# jura.net
KiCad netlist of a schematic drawn in EAGLE
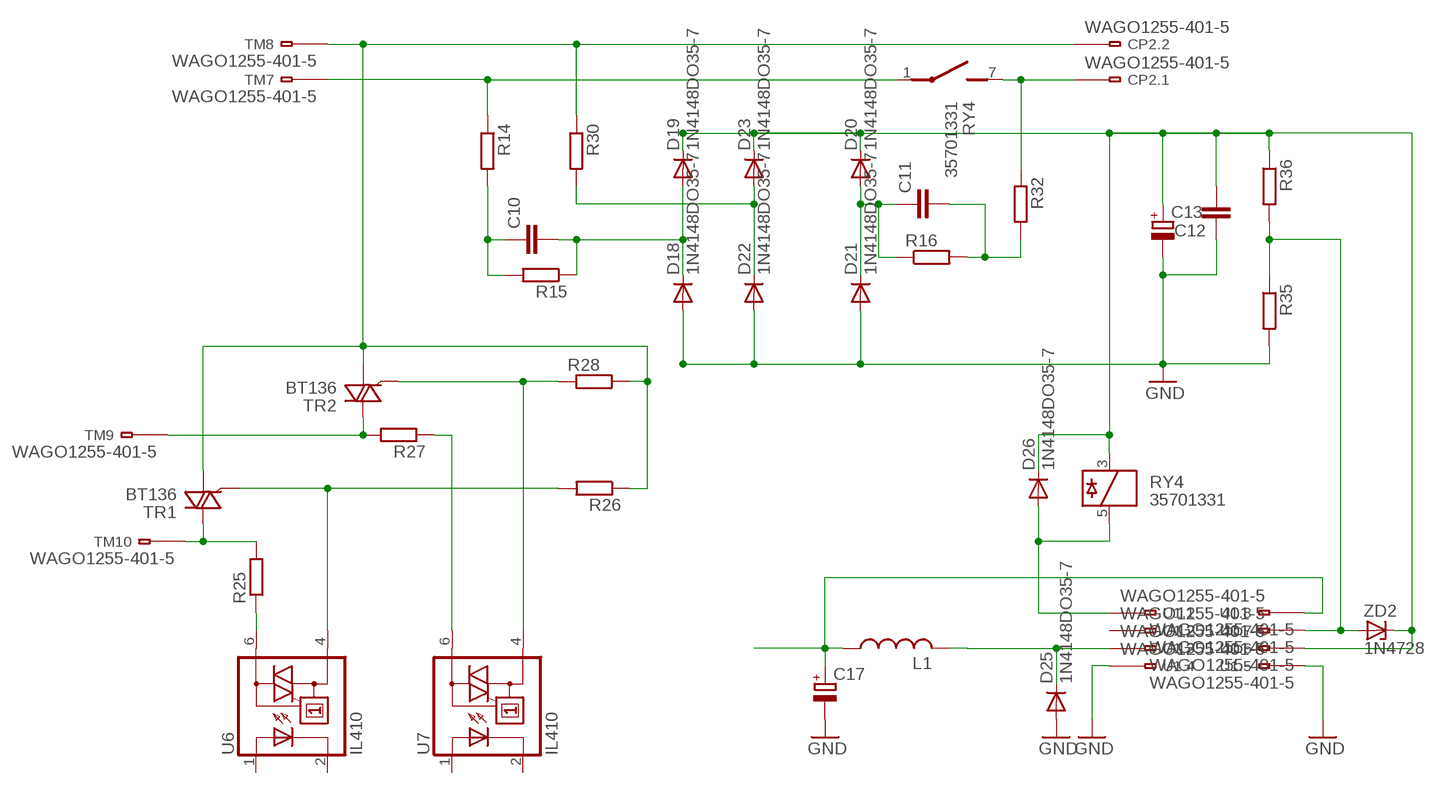
[diagram p0: schematic, sheet 1]

(export (version "E")
  (design (tool "Eeschema 10.0.6"))
  (components
    (comp (ref "C10")
      (value "C-EU025-025X050")
      (footprint "eagle-import:C025-025X050")
      (libsource (lib "eagle-import") (part "C-EU025-025X050"))
    )
    (comp (ref "C11")
      (value "C-EU025-025X050")
      (footprint "eagle-import:C025-025X050")
      (libsource (lib "eagle-import") (part "C-EU025-025X050"))
    )
    (comp (ref "C12")
      (value "C-EU025-025X050")
      (footprint "eagle-import:C025-025X050")
      (libsource (lib "eagle-import") (part "C-EU025-025X050"))
    )
    (comp (ref "C13")
      (value "CPOL-EUE2-4")
      (footprint "eagle-import:E2-4")
      (libsource (lib "eagle-import") (part "CPOL-EUE2-4"))
    )
    (comp (ref "C17")
      (value "CPOL-EUE2-4")
      (footprint "eagle-import:E2-4")
      (libsource (lib "eagle-import") (part "CPOL-EUE2-4"))
    )
    (comp (ref "CP2.1")
      (value "WAGO1255-401-5")
      (footprint "eagle-import:255-401-5")
      (fields (field (name "MPN") "255-401"))
      (libsource (lib "eagle-import") (part "WAGO1255-401-5"))
    )
    (comp (ref "CP2.2")
      (value "WAGO1255-401-5")
      (footprint "eagle-import:255-401-5")
      (fields (field (name "MPN") "255-401"))
      (libsource (lib "eagle-import") (part "WAGO1255-401-5"))
    )
    (comp (ref "D18")
      (value "1N4148DO35-7")
      (footprint "eagle-import:DO35-7")
      (libsource (lib "eagle-import") (part "1N4148DO35-7"))
    )
    (comp (ref "D19")
      (value "1N4148DO35-7")
      (footprint "eagle-import:DO35-7")
      (libsource (lib "eagle-import") (part "1N4148DO35-7"))
    )
    (comp (ref "D20")
      (value "1N4148DO35-7")
      (footprint "eagle-import:DO35-7")
      (libsource (lib "eagle-import") (part "1N4148DO35-7"))
    )
    (comp (ref "D21")
      (value "1N4148DO35-7")
      (footprint "eagle-import:DO35-7")
      (libsource (lib "eagle-import") (part "1N4148DO35-7"))
    )
    (comp (ref "D22")
      (value "1N4148DO35-7")
      (footprint "eagle-import:DO35-7")
      (libsource (lib "eagle-import") (part "1N4148DO35-7"))
    )
    (comp (ref "D23")
      (value "1N4148DO35-7")
      (footprint "eagle-import:DO35-7")
      (libsource (lib "eagle-import") (part "1N4148DO35-7"))
    )
    (comp (ref "D25")
      (value "1N4148DO35-7")
      (footprint "eagle-import:DO35-7")
      (libsource (lib "eagle-import") (part "1N4148DO35-7"))
    )
    (comp (ref "D26")
      (value "1N4148DO35-7")
      (footprint "eagle-import:DO35-7")
      (libsource (lib "eagle-import") (part "1N4148DO35-7"))
    )
    (comp (ref "L1")
      (value "L-US0204/7")
      (footprint "eagle-import:0204_7")
      (libsource (lib "eagle-import") (part "L-US0204/7"))
    )
    (comp (ref "R14")
      (value "R-EU_0204/7")
      (footprint "eagle-import:0204_7")
      (libsource (lib "eagle-import") (part "R-EU_0204/7"))
    )
    (comp (ref "R15")
      (value "R-EU_0204/7")
      (footprint "eagle-import:0204_7")
      (libsource (lib "eagle-import") (part "R-EU_0204/7"))
    )
    (comp (ref "R16")
      (value "R-EU_0204/7")
      (footprint "eagle-import:0204_7")
      (libsource (lib "eagle-import") (part "R-EU_0204/7"))
    )
    (comp (ref "R25")
      (value "R-EU_0204/7")
      (footprint "eagle-import:0204_7")
      (libsource (lib "eagle-import") (part "R-EU_0204/7"))
    )
    (comp (ref "R26")
      (value "R-EU_0204/7")
      (footprint "eagle-import:0204_7")
      (libsource (lib "eagle-import") (part "R-EU_0204/7"))
    )
    (comp (ref "R27")
      (value "R-EU_0204/7")
      (footprint "eagle-import:0204_7")
      (libsource (lib "eagle-import") (part "R-EU_0204/7"))
    )
    (comp (ref "R28")
      (value "R-EU_0204/7")
      (footprint "eagle-import:0204_7")
      (libsource (lib "eagle-import") (part "R-EU_0204/7"))
    )
    (comp (ref "R30")
      (value "R-EU_0204/7")
      (footprint "eagle-import:0204_7")
      (libsource (lib "eagle-import") (part "R-EU_0204/7"))
    )
    (comp (ref "R32")
      (value "R-EU_0204/7")
      (footprint "eagle-import:0204_7")
      (libsource (lib "eagle-import") (part "R-EU_0204/7"))
    )
    (comp (ref "R35")
      (value "R-EU_0204/7")
      (footprint "eagle-import:0204_7")
      (libsource (lib "eagle-import") (part "R-EU_0204/7"))
    )
    (comp (ref "R36")
      (value "R-EU_0204/7")
      (footprint "eagle-import:0204_7")
      (libsource (lib "eagle-import") (part "R-EU_0204/7"))
    )
    (comp (ref "RY4")
      (value "35701331")
      (footprint "eagle-import:REED")
      (libsource (lib "eagle-import") (part "35701331"))
    )
    (comp (ref "TM7")
      (value "WAGO1255-401-5")
      (footprint "eagle-import:255-401-5")
      (fields (field (name "MPN") "255-401"))
      (libsource (lib "eagle-import") (part "WAGO1255-401-5"))
    )
    (comp (ref "TM8")
      (value "WAGO1255-401-5")
      (footprint "eagle-import:255-401-5")
      (fields (field (name "MPN") "255-401"))
      (libsource (lib "eagle-import") (part "WAGO1255-401-5"))
    )
    (comp (ref "TM9")
      (value "WAGO1255-401-5")
      (footprint "eagle-import:255-401-5")
      (fields (field (name "MPN") "255-401"))
      (libsource (lib "eagle-import") (part "WAGO1255-401-5"))
    )
    (comp (ref "TM10")
      (value "WAGO1255-401-5")
      (footprint "eagle-import:255-401-5")
      (fields (field (name "MPN") "255-401"))
      (libsource (lib "eagle-import") (part "WAGO1255-401-5"))
    )
    (comp (ref "TR1")
      (value "BT136")
      (footprint "eagle-import:TO220AB")
      (libsource (lib "eagle-import") (part "BT136"))
    )
    (comp (ref "TR2")
      (value "BT136")
      (footprint "eagle-import:TO220AB")
      (libsource (lib "eagle-import") (part "BT136"))
    )
    (comp (ref "U1.1")
      (value "WAGO1255-401-5")
      (footprint "eagle-import:255-401-5")
      (fields (field (name "MPN") "255-401"))
      (libsource (lib "eagle-import") (part "WAGO1255-401-5"))
    )
    (comp (ref "U1.2")
      (value "WAGO1255-401-5")
      (footprint "eagle-import:255-401-5")
      (fields (field (name "MPN") "255-401"))
      (libsource (lib "eagle-import") (part "WAGO1255-401-5"))
    )
    (comp (ref "U1.3")
      (value "WAGO1255-401-5")
      (footprint "eagle-import:255-401-5")
      (fields (field (name "MPN") "255-401"))
      (libsource (lib "eagle-import") (part "WAGO1255-401-5"))
    )
    (comp (ref "U1.4")
      (value "WAGO1255-401-5")
      (footprint "eagle-import:255-401-5")
      (fields (field (name "MPN") "255-401"))
      (libsource (lib "eagle-import") (part "WAGO1255-401-5"))
    )
    (comp (ref "U1.5")
      (value "WAGO1255-401-5")
      (footprint "eagle-import:255-401-5")
      (fields (field (name "MPN") "255-401"))
      (libsource (lib "eagle-import") (part "WAGO1255-401-5"))
    )
    (comp (ref "U1.6")
      (value "WAGO1255-401-5")
      (footprint "eagle-import:255-401-5")
      (fields (field (name "MPN") "255-401"))
      (libsource (lib "eagle-import") (part "WAGO1255-401-5"))
    )
    (comp (ref "U1.7")
      (value "WAGO1255-401-5")
      (footprint "eagle-import:255-401-5")
      (fields (field (name "MPN") "255-401"))
      (libsource (lib "eagle-import") (part "WAGO1255-401-5"))
    )
    (comp (ref "U1.8")
      (value "WAGO1255-401-5")
      (footprint "eagle-import:255-401-5")
      (fields (field (name "MPN") "255-401"))
      (libsource (lib "eagle-import") (part "WAGO1255-401-5"))
    )
    (comp (ref "U6")
      (value "IL410")
      (footprint "eagle-import:DIL06")
      (fields (field (name "MF") "VISHAY/TELEFUNKEN"))
      (libsource (lib "eagle-import") (part "IL410"))
    )
    (comp (ref "U7")
      (value "IL410")
      (footprint "eagle-import:DIL06")
      (fields (field (name "MF") "VISHAY/TELEFUNKEN"))
      (libsource (lib "eagle-import") (part "IL410"))
    )
    (comp (ref "ZD2")
      (value "1N4728")
      (footprint "eagle-import:DO41Z10")
      (libsource (lib "eagle-import") (part "1N4728"))
    )
  )
  (nets
    (net (code "1") (name "GND") (class "Default")
      (node (ref "C12") (pin "1") (pinfunction "1_1") (pintype "passive"))
      (node (ref "C13") (pin "-") (pinfunction "-_-") (pintype "passive"))
      (node (ref "C17") (pin "-") (pinfunction "-_-") (pintype "passive"))
      (node (ref "D18") (pin "A") (pinfunction "A_A") (pintype "passive"))
      (node (ref "D21") (pin "A") (pinfunction "A_A") (pintype "passive"))
      (node (ref "D22") (pin "A") (pinfunction "A_A") (pintype "passive"))
      (node (ref "D25") (pin "A") (pinfunction "A_A") (pintype "passive"))
      (node (ref "R35") (pin "2") (pinfunction "2_2") (pintype "passive"))
      (node (ref "U1.4") (pin "B1") (pinfunction "B1_B1") (pintype "passive"))
      (node (ref "U1.5") (pin "B1") (pinfunction "B1_B1") (pintype "passive"))
    )
    (net (code "2") (name "Net-(C10-Pad1)") (class "Default")
      (node (ref "C10") (pin "1") (pinfunction "1_1") (pintype "passive"))
      (node (ref "R14") (pin "2") (pinfunction "2_2") (pintype "passive"))
      (node (ref "R15") (pin "2") (pinfunction "2_2") (pintype "passive"))
    )
    (net (code "3") (name "Net-(C10-Pad2)") (class "Default")
      (node (ref "C10") (pin "2") (pinfunction "2_2") (pintype "passive"))
      (node (ref "D18") (pin "C") (pinfunction "C_C") (pintype "passive"))
      (node (ref "D19") (pin "A") (pinfunction "A_A") (pintype "passive"))
      (node (ref "R15") (pin "1") (pinfunction "1_1") (pintype "passive"))
    )
    (net (code "4") (name "Net-(C11-Pad1)") (class "Default")
      (node (ref "C11") (pin "1") (pinfunction "1_1") (pintype "passive"))
      (node (ref "D20") (pin "A") (pinfunction "A_A") (pintype "passive"))
      (node (ref "D21") (pin "C") (pinfunction "C_C") (pintype "passive"))
      (node (ref "R16") (pin "1") (pinfunction "1_1") (pintype "passive"))
    )
    (net (code "5") (name "Net-(C11-Pad2)") (class "Default")
      (node (ref "C11") (pin "2") (pinfunction "2_2") (pintype "passive"))
      (node (ref "R16") (pin "2") (pinfunction "2_2") (pintype "passive"))
      (node (ref "R32") (pin "2") (pinfunction "2_2") (pintype "passive"))
    )
    (net (code "6") (name "Net-(C12-Pad2)") (class "Default")
      (node (ref "C12") (pin "2") (pinfunction "2_2") (pintype "passive"))
      (node (ref "C13") (pin "+") (pinfunction "+_+") (pintype "passive"))
      (node (ref "D19") (pin "C") (pinfunction "C_C") (pintype "passive"))
      (node (ref "D20") (pin "C") (pinfunction "C_C") (pintype "passive"))
      (node (ref "D23") (pin "C") (pinfunction "C_C") (pintype "passive"))
      (node (ref "D26") (pin "C") (pinfunction "C_C") (pintype "passive"))
      (node (ref "R36") (pin "1") (pinfunction "1_1") (pintype "passive"))
      (node (ref "RY4") (pin "3") (pinfunction "3_3") (pintype "passive"))
      (node (ref "U1.6") (pin "B1") (pinfunction "B1_B1") (pintype "passive"))
      (node (ref "ZD2") (pin "C") (pinfunction "C_C") (pintype "passive"))
    )
    (net (code "7") (name "Net-(C17-Pad+)") (class "Default")
      (node (ref "C17") (pin "+") (pinfunction "+_+") (pintype "passive"))
      (node (ref "L1") (pin "1") (pinfunction "1_1") (pintype "passive"))
      (node (ref "U1.8") (pin "B1") (pinfunction "B1_B1") (pintype "passive"))
    )
    (net (code "8") (name "Net-(D22-PadC)") (class "Default")
      (node (ref "D22") (pin "C") (pinfunction "C_C") (pintype "passive"))
      (node (ref "D23") (pin "A") (pinfunction "A_A") (pintype "passive"))
      (node (ref "R30") (pin "2") (pinfunction "2_2") (pintype "passive"))
    )
    (net (code "9") (name "Net-(D25-PadC)") (class "Default")
      (node (ref "D25") (pin "C") (pinfunction "C_C") (pintype "passive"))
      (node (ref "L1") (pin "2") (pinfunction "2_2") (pintype "passive"))
      (node (ref "U1.3") (pin "B1") (pinfunction "B1_B1") (pintype "passive"))
    )
    (net (code "10") (name "Net-(D26-PadA)") (class "Default")
      (node (ref "D26") (pin "A") (pinfunction "A_A") (pintype "passive"))
      (node (ref "RY4") (pin "5") (pinfunction "5_5") (pintype "passive"))
      (node (ref "U1.1") (pin "B1") (pinfunction "B1_B1") (pintype "passive"))
    )
    (net (code "11") (name "Net-(R35-Pad1)") (class "Default")
      (node (ref "R35") (pin "1") (pinfunction "1_1") (pintype "passive"))
      (node (ref "R36") (pin "2") (pinfunction "2_2") (pintype "passive"))
      (node (ref "U1.7") (pin "B1") (pinfunction "B1_B1") (pintype "passive"))
      (node (ref "ZD2") (pin "A") (pinfunction "A_A") (pintype "passive"))
    )
    (net (code "12") (name "Net-(RY4B-P)") (class "Default")
      (node (ref "R14") (pin "1") (pinfunction "1_1") (pintype "passive"))
      (node (ref "RY4") (pin "1") (pinfunction "P_1") (pintype "passive"))
      (node (ref "TM7") (pin "B1") (pinfunction "B1_B1") (pintype "passive"))
    )
    (net (code "13") (name "Net-(RY4B-S)") (class "Default")
      (node (ref "CP2.1") (pin "B1") (pinfunction "B1_B1") (pintype "passive"))
      (node (ref "R32") (pin "1") (pinfunction "1_1") (pintype "passive"))
      (node (ref "RY4") (pin "7") (pinfunction "S_7") (pintype "passive"))
    )
    (net (code "14") (name "Net-(TR1-A1)") (class "Default")
      (node (ref "CP2.2") (pin "B1") (pinfunction "B1_B1") (pintype "passive"))
      (node (ref "R26") (pin "1") (pinfunction "1_1") (pintype "passive"))
      (node (ref "R28") (pin "2") (pinfunction "2_2") (pintype "passive"))
      (node (ref "R30") (pin "1") (pinfunction "1_1") (pintype "passive"))
      (node (ref "TM8") (pin "B1") (pinfunction "B1_B1") (pintype "passive"))
      (node (ref "TR1") (pin "1") (pinfunction "A1_1") (pintype "passive"))
      (node (ref "TR2") (pin "1") (pinfunction "A1_1") (pintype "passive"))
    )
    (net (code "15") (name "Net-(TR1-A2)") (class "Default")
      (node (ref "R25") (pin "2") (pinfunction "2_2") (pintype "passive"))
      (node (ref "TM10") (pin "B1") (pinfunction "B1_B1") (pintype "passive"))
      (node (ref "TR1") (pin "2") (pinfunction "A2_2") (pintype "passive"))
    )
    (net (code "16") (name "Net-(TR1-G)") (class "Default")
      (node (ref "R26") (pin "2") (pinfunction "2_2") (pintype "passive"))
      (node (ref "TR1") (pin "3") (pinfunction "G_3") (pintype "passive"))
      (node (ref "U6") (pin "4") (pinfunction "A1_4") (pintype "passive"))
    )
    (net (code "17") (name "Net-(TR2-A2)") (class "Default")
      (node (ref "R27") (pin "2") (pinfunction "2_2") (pintype "passive"))
      (node (ref "TM9") (pin "B1") (pinfunction "B1_B1") (pintype "passive"))
      (node (ref "TR2") (pin "2") (pinfunction "A2_2") (pintype "passive"))
    )
    (net (code "18") (name "Net-(TR2-G)") (class "Default")
      (node (ref "R28") (pin "1") (pinfunction "1_1") (pintype "passive"))
      (node (ref "TR2") (pin "3") (pinfunction "G_3") (pintype "passive"))
      (node (ref "U7") (pin "4") (pinfunction "A1_4") (pintype "passive"))
    )
    (net (code "19") (name "Net-(U6-A2)") (class "Default")
      (node (ref "R25") (pin "1") (pinfunction "1_1") (pintype "passive"))
      (node (ref "U6") (pin "6") (pinfunction "A2_6") (pintype "passive"))
    )
    (net (code "20") (name "Net-(U7-A2)") (class "Default")
      (node (ref "R27") (pin "1") (pinfunction "1_1") (pintype "passive"))
      (node (ref "U7") (pin "6") (pinfunction "A2_6") (pintype "passive"))
    )
    (net (code "21") (name "unconnected-(CP2.1-PadA1)") (class "Default")
      (node (ref "CP2.1") (pin "A1") (pinfunction "A1_A1") (pintype "passive"))
    )
    (net (code "22") (name "unconnected-(CP2.2-PadA1)") (class "Default")
      (node (ref "CP2.2") (pin "A1") (pinfunction "A1_A1") (pintype "passive"))
    )
    (net (code "23") (name "unconnected-(TM7-PadA1)") (class "Default")
      (node (ref "TM7") (pin "A1") (pinfunction "A1_A1") (pintype "passive"))
    )
    (net (code "24") (name "unconnected-(TM8-PadA1)") (class "Default")
      (node (ref "TM8") (pin "A1") (pinfunction "A1_A1") (pintype "passive"))
    )
    (net (code "25") (name "unconnected-(TM9-PadA1)") (class "Default")
      (node (ref "TM9") (pin "A1") (pinfunction "A1_A1") (pintype "passive"))
    )
    (net (code "26") (name "unconnected-(TM10-PadA1)") (class "Default")
      (node (ref "TM10") (pin "A1") (pinfunction "A1_A1") (pintype "passive"))
    )
    (net (code "27") (name "unconnected-(U1.1-PadA1)") (class "Default")
      (node (ref "U1.1") (pin "A1") (pinfunction "A1_A1") (pintype "passive"))
    )
    (net (code "28") (name "unconnected-(U1.2-PadA1)") (class "Default")
      (node (ref "U1.2") (pin "A1") (pinfunction "A1_A1") (pintype "passive"))
    )
    (net (code "29") (name "unconnected-(U1.2-PadB1)") (class "Default")
      (node (ref "U1.2") (pin "B1") (pinfunction "B1_B1") (pintype "passive"))
    )
    (net (code "30") (name "unconnected-(U1.3-PadA1)") (class "Default")
      (node (ref "U1.3") (pin "A1") (pinfunction "A1_A1") (pintype "passive"))
    )
    (net (code "31") (name "unconnected-(U1.4-PadA1)") (class "Default")
      (node (ref "U1.4") (pin "A1") (pinfunction "A1_A1") (pintype "passive"))
    )
    (net (code "32") (name "unconnected-(U1.5-PadA1)") (class "Default")
      (node (ref "U1.5") (pin "A1") (pinfunction "A1_A1") (pintype "passive"))
    )
    (net (code "33") (name "unconnected-(U1.6-PadA1)") (class "Default")
      (node (ref "U1.6") (pin "A1") (pinfunction "A1_A1") (pintype "passive"))
    )
    (net (code "34") (name "unconnected-(U1.7-PadA1)") (class "Default")
      (node (ref "U1.7") (pin "A1") (pinfunction "A1_A1") (pintype "passive"))
    )
    (net (code "35") (name "unconnected-(U1.8-PadA1)") (class "Default")
      (node (ref "U1.8") (pin "A1") (pinfunction "A1_A1") (pintype "passive"))
    )
    (net (code "36") (name "unconnected-(U6-A-Pad1)") (class "Default")
      (node (ref "U6") (pin "1") (pinfunction "A_1") (pintype "passive"))
    )
    (net (code "37") (name "unconnected-(U6-C-Pad2)") (class "Default")
      (node (ref "U6") (pin "2") (pinfunction "C_2") (pintype "passive"))
    )
    (net (code "38") (name "unconnected-(U7-A-Pad1)") (class "Default")
      (node (ref "U7") (pin "1") (pinfunction "A_1") (pintype "passive"))
    )
    (net (code "39") (name "unconnected-(U7-C-Pad2)") (class "Default")
      (node (ref "U7") (pin "2") (pinfunction "C_2") (pintype "passive"))
    )
  )
)
